# joystick.net
KiCad netlist of a schematic drawn in EAGLE
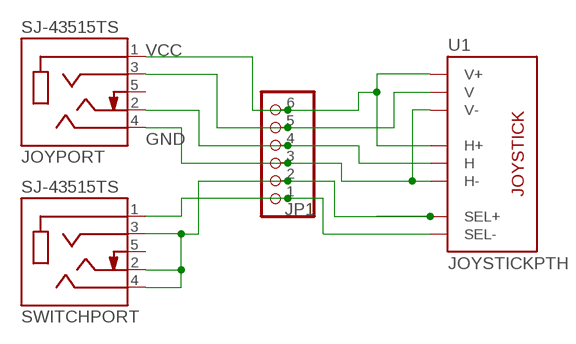
[diagram p0: schematic, sheet 1]

(export (version "E")
  (design (tool "Eeschema 10.0.6"))
  (components
    (comp (ref "JOYPORT")
      (value "SJ-43515TS")
      (footprint "eagle-import:CUI_SJ-43515TS")
      (fields (field (name "MF") "CUI Devices"))
      (libsource (lib "eagle-import") (part "SJ-43515TS"))
    )
    (comp (ref "JP1")
      (value "PINHD-1X6B")
      (footprint "eagle-import:1X06-BIG")
      (libsource (lib "eagle-import") (part "PINHD-1X6B"))
    )
    (comp (ref "SWITCHPORT")
      (value "SJ-43515TS")
      (footprint "eagle-import:CUI_SJ-43515TS")
      (fields (field (name "MF") "CUI Devices"))
      (libsource (lib "eagle-import") (part "SJ-43515TS"))
    )
    (comp (ref "U1")
      (value "JOYSTICKPTH")
      (footprint "eagle-import:JOYSTICK")
      (libsource (lib "eagle-import") (part "JOYSTICKPTH"))
    )
  )
  (nets
    (net (code "1") (name "/GND") (class "Default")
      (node (ref "JOYPORT") (pin "4") (pinfunction "RING2_4") (pintype "passive"))
      (node (ref "JP1") (pin "3") (pinfunction "3_3") (pintype "passive"))
      (node (ref "U1") (pin "H3") (pinfunction "H-_H3") (pintype "bidirectional"))
      (node (ref "U1") (pin "V3") (pinfunction "V-_V3") (pintype "bidirectional"))
    )
    (net (code "2") (name "/VCC") (class "Default")
      (node (ref "JOYPORT") (pin "1") (pinfunction "SLEEVE_1") (pintype "passive"))
      (node (ref "JP1") (pin "6") (pinfunction "6_6") (pintype "passive"))
      (node (ref "U1") (pin "H1") (pinfunction "H+_H1") (pintype "bidirectional"))
      (node (ref "U1") (pin "V1") (pinfunction "V+_V1") (pintype "bidirectional"))
    )
    (net (code "3") (name "Net-(JOYPORT-RING1)") (class "Default")
      (node (ref "JOYPORT") (pin "3") (pinfunction "RING1_3") (pintype "passive"))
      (node (ref "JP1") (pin "5") (pinfunction "5_5") (pintype "passive"))
      (node (ref "U1") (pin "V2") (pinfunction "V_V2") (pintype "bidirectional"))
    )
    (net (code "4") (name "Net-(JOYPORT-TIP)") (class "Default")
      (node (ref "JOYPORT") (pin "2") (pinfunction "TIP_2") (pintype "passive"))
      (node (ref "JP1") (pin "4") (pinfunction "4_4") (pintype "passive"))
      (node (ref "U1") (pin "H2") (pinfunction "H_H2") (pintype "bidirectional"))
    )
    (net (code "5") (name "Net-(SWITCHPORT-RING1)") (class "Default")
      (node (ref "JP1") (pin "2") (pinfunction "2_2") (pintype "passive"))
      (node (ref "SWITCHPORT") (pin "2") (pinfunction "TIP_2") (pintype "passive"))
      (node (ref "SWITCHPORT") (pin "3") (pinfunction "RING1_3") (pintype "passive"))
      (node (ref "SWITCHPORT") (pin "4") (pinfunction "RING2_4") (pintype "passive"))
      (node (ref "U1") (pin "B1A") (pinfunction "SEL+_B1A") (pintype "bidirectional"))
    )
    (net (code "6") (name "Net-(SWITCHPORT-SLEEVE)") (class "Default")
      (node (ref "JP1") (pin "1") (pinfunction "1_1") (pintype "passive"))
      (node (ref "SWITCHPORT") (pin "1") (pinfunction "SLEEVE_1") (pintype "passive"))
      (node (ref "U1") (pin "B2A") (pinfunction "SEL-_B2A") (pintype "bidirectional"))
    )
    (net (code "7") (name "unconnected-(JOYPORT-TIP_SWITCH-Pad5)") (class "Default")
      (node (ref "JOYPORT") (pin "5") (pinfunction "TIP_SWITCH_5") (pintype "passive"))
    )
    (net (code "8") (name "unconnected-(SWITCHPORT-TIP_SWITCH-Pad5)") (class "Default")
      (node (ref "SWITCHPORT") (pin "5") (pinfunction "TIP_SWITCH_5") (pintype "passive"))
    )
  )
)
